# LM2596_BuckConverter.net
KiCad netlist of a schematic drawn in Altium Designer
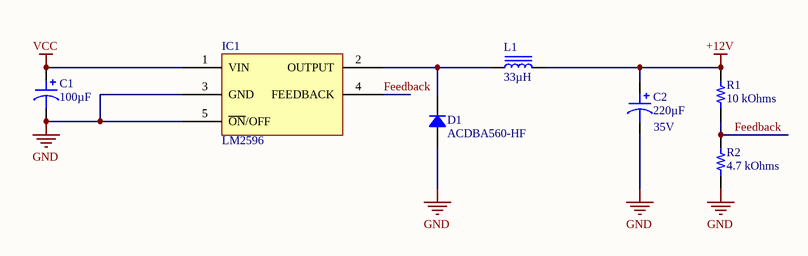
[diagram p0: LM2596_BuckConverter.SchDoc]

(export (version "E")
  (design (tool "Eeschema 10.0.6"))
  (components
    (comp (ref "C1")
      (value "100µF")
      (footprint "CAP TH ALUM ELEC D8.00mm S3.50mm H12.50mm")
      (description "CAP ALUM 100UF 20% 63V RADIAL")
      (fields
        (field (name "PART NUMBER") "ECA-1JM101")
        (field (name "MANUFACTURER") "Panasonic Electronic Components")
      )
      (libsource (lib "Celestial Altium Library - altium_library") (part "Polarised Capacitor"))
    )
    (comp (ref "C2")
      (value "220µF")
      (footprint "CAP TH ALUM ELEC D8.00mm S3.50mm H12.50mm")
      (description "CAP ALUM 220UF 20% 35V RADIAL")
      (fields
        (field (name "PART NUMBER") "ECA-1VM221")
        (field (name "MANUFACTURER") "Panasonic Electronic Components")
        (field (name "VOLTAGE - RATED") "35V")
      )
      (libsource (lib "Celestial Altium Library - altium_library") (part "Polarised Capacitor"))
    )
    (comp (ref "D1")
      (value "ACDBA560-HF")
      (footprint "DO214AC SMA")
      (description "DIODE SCHOTTKY 60V 5A DO214AC")
      (fields (field (name "MANUFACTURER") "Comchip Technology"))
      (libsource (lib "Celestial Altium Library - altium_library") (part "Diode"))
    )
    (comp (ref "IC1") (value "LM2596") (footprint "D2PAK") (libsource (lib "AltiumLive") (part "LM2596")))
    (comp (ref "L1")
      (value "33µH")
      (footprint "BOURNS SRR1280")
      (description "FIXED IND 33UH 3.5A 57 MOHM SMD")
      (fields (field (name "PART NUMBER") "SRR1280-330M") (field (name "MANUFACTURER") "Bourns Inc."))
      (libsource (lib "Celestial Altium Library - altium_library") (part "Inductor"))
    )
    (comp (ref "R1")
      (value "10 kOhms")
      (footprint "RES 0805_2012")
      (description "CRGP 0805 10K 1%")
      (fields
        (field (name "PART NUMBER") "CRGP0805F10K")
        (field (name "MANUFACTURER") "TE Connectivity Passive Product")
      )
      (libsource (lib "Celestial Altium Library - altium_library") (part "Resistor"))
    )
    (comp (ref "R2")
      (value "4.7 kOhms")
      (footprint "RES 0805_2012")
      (description "CRGP 0805 4K7 1%")
      (fields
        (field (name "PART NUMBER") "CRGP0805F4K7")
        (field (name "MANUFACTURER") "TE Connectivity Passive Product")
      )
      (libsource (lib "Celestial Altium Library - altium_library") (part "Resistor"))
    )
  )
  (nets
    (net (code "1") (name "+12V") (class "Default")
      (node (ref "C2") (pin "1") (pinfunction "1_1") (pintype "passive"))
      (node (ref "L1") (pin "2") (pinfunction "2_2") (pintype "passive"))
      (node (ref "R1") (pin "2") (pinfunction "2_2") (pintype "passive"))
    )
    (net (code "2") (name "/Feedback") (class "Default")
      (node (ref "IC1") (pin "4") (pinfunction "FEEDBACK_4") (pintype "passive"))
      (node (ref "R1") (pin "1") (pinfunction "1_1") (pintype "passive"))
      (node (ref "R2") (pin "1") (pinfunction "1_1") (pintype "passive"))
    )
    (net (code "3") (name "GND") (class "Default")
      (node (ref "C1") (pin "2") (pinfunction "2_2") (pintype "passive"))
      (node (ref "C2") (pin "2") (pinfunction "2_2") (pintype "passive"))
      (node (ref "D1") (pin "1") (pinfunction "1_1") (pintype "passive"))
      (node (ref "IC1") (pin "3") (pinfunction "GND_3") (pintype "passive"))
      (node (ref "IC1") (pin "5") (pinfunction "~{ON}/OFF_5") (pintype "passive"))
      (node (ref "R2") (pin "2") (pinfunction "2_2") (pintype "passive"))
    )
    (net (code "4") (name "Net-(IC1-OUTPUT)") (class "Default")
      (node (ref "D1") (pin "2") (pinfunction "2_2") (pintype "passive"))
      (node (ref "IC1") (pin "2") (pinfunction "OUTPUT_2") (pintype "passive"))
      (node (ref "L1") (pin "1") (pinfunction "1_1") (pintype "passive"))
    )
    (net (code "5") (name "VCC") (class "Default")
      (node (ref "C1") (pin "1") (pinfunction "1_1") (pintype "passive"))
      (node (ref "IC1") (pin "1") (pinfunction "VIN_1") (pintype "passive"))
    )
  )
)
